# drutest2.net
KiCad netlist of a schematic drawn in EAGLE
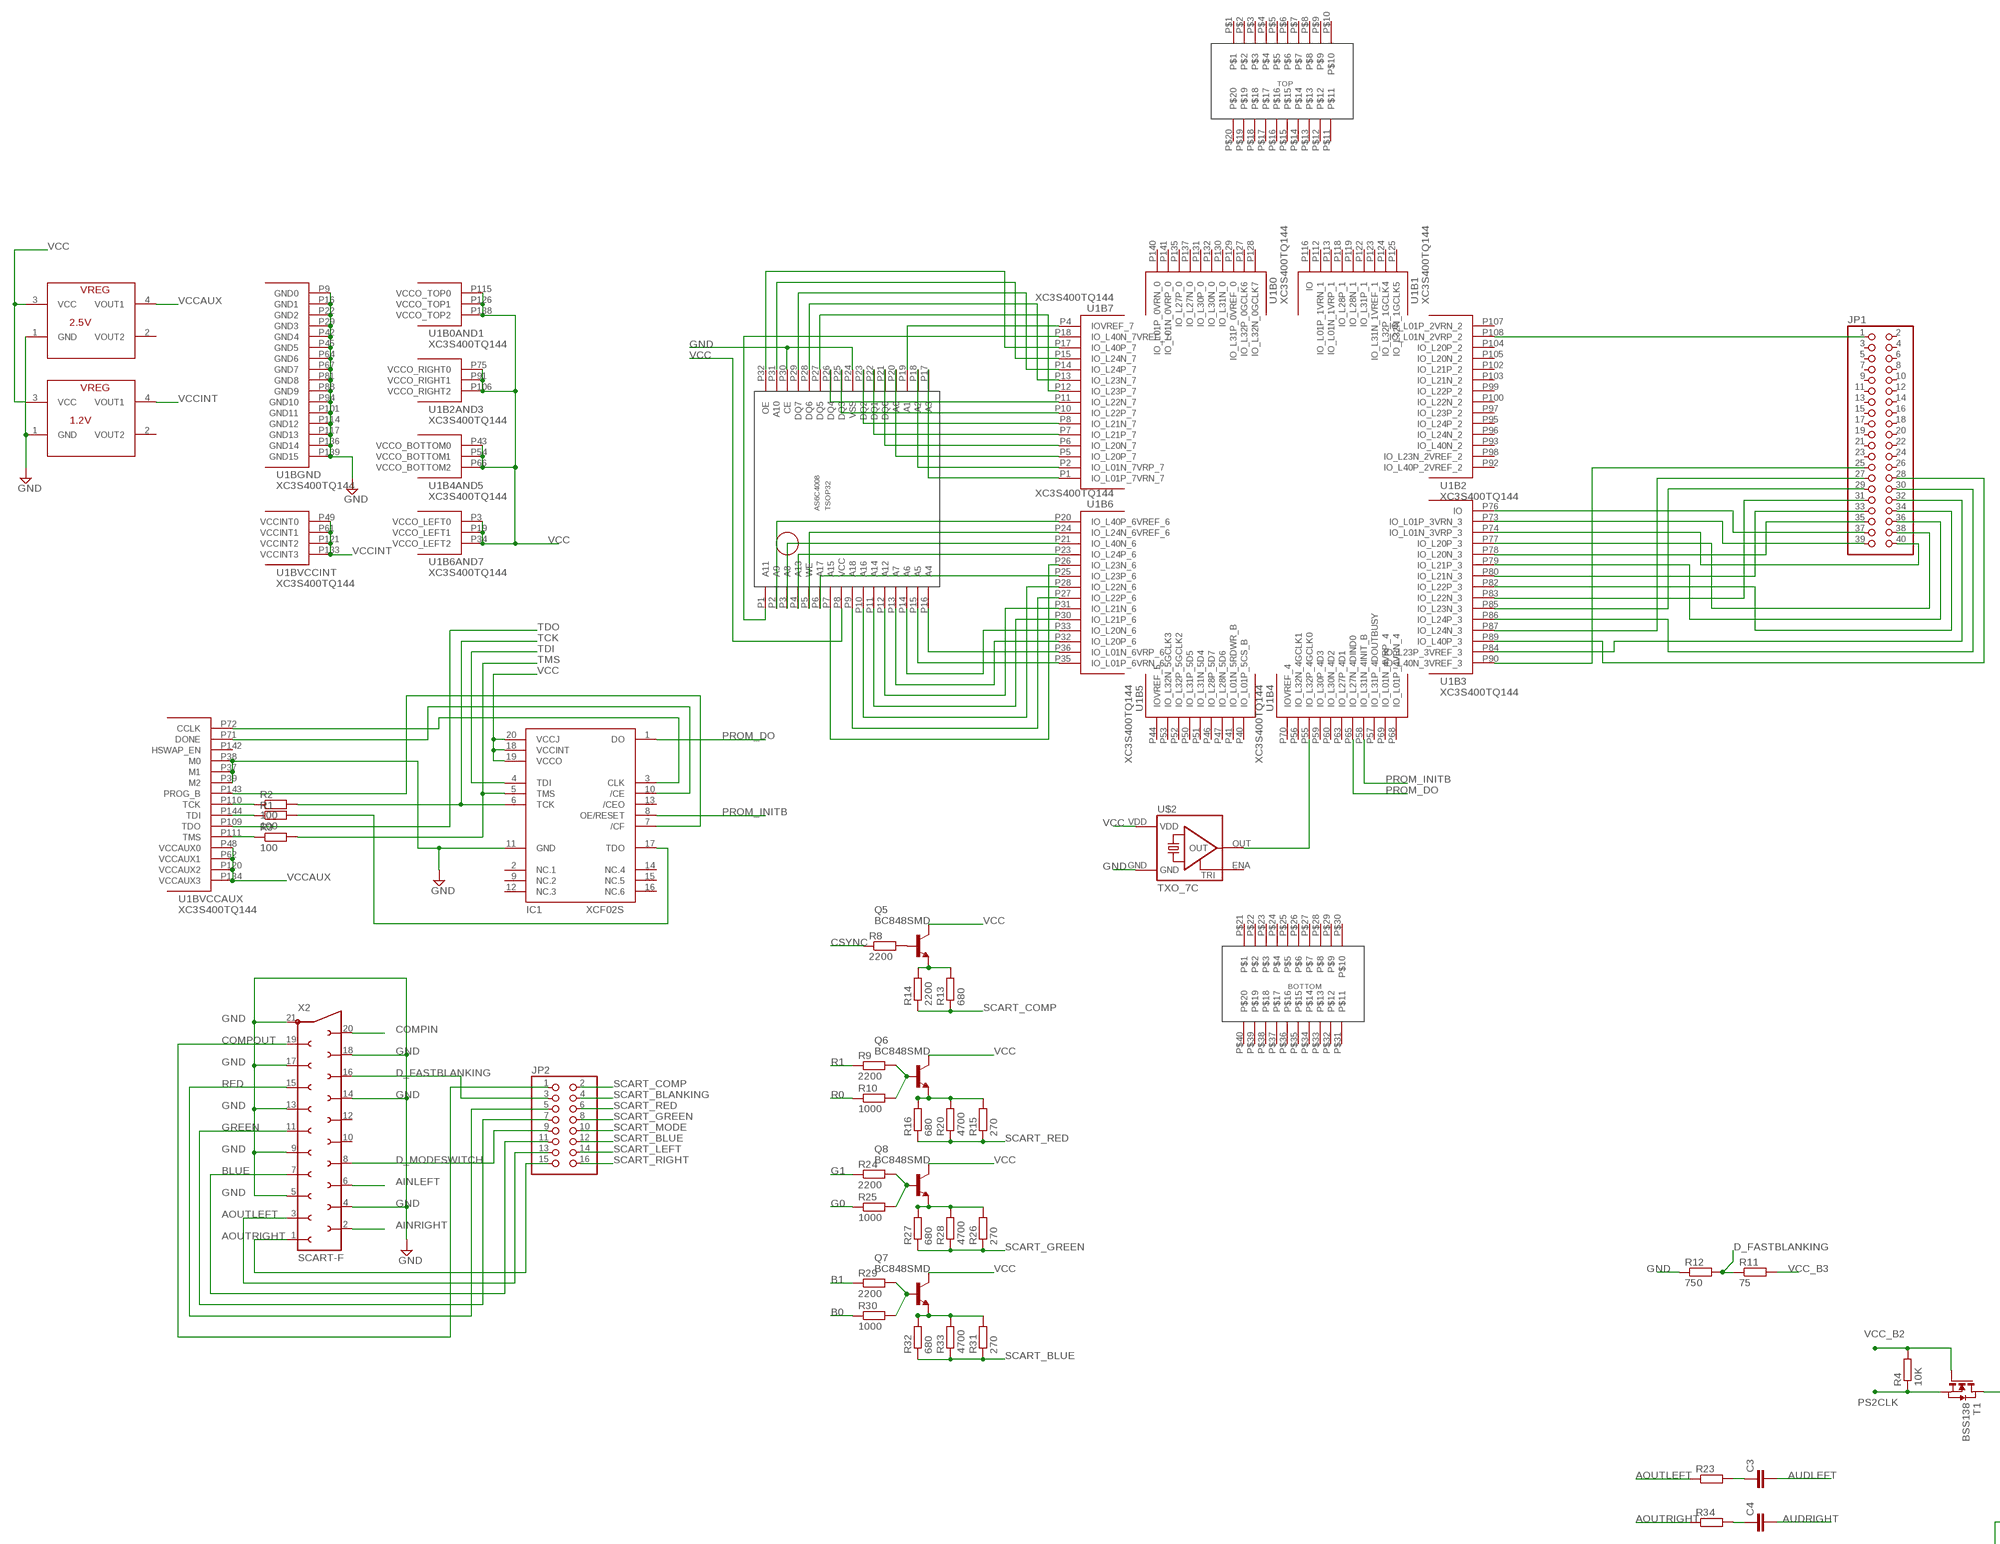
[diagram p0: schematic, sheet 1, part 1 of 2]
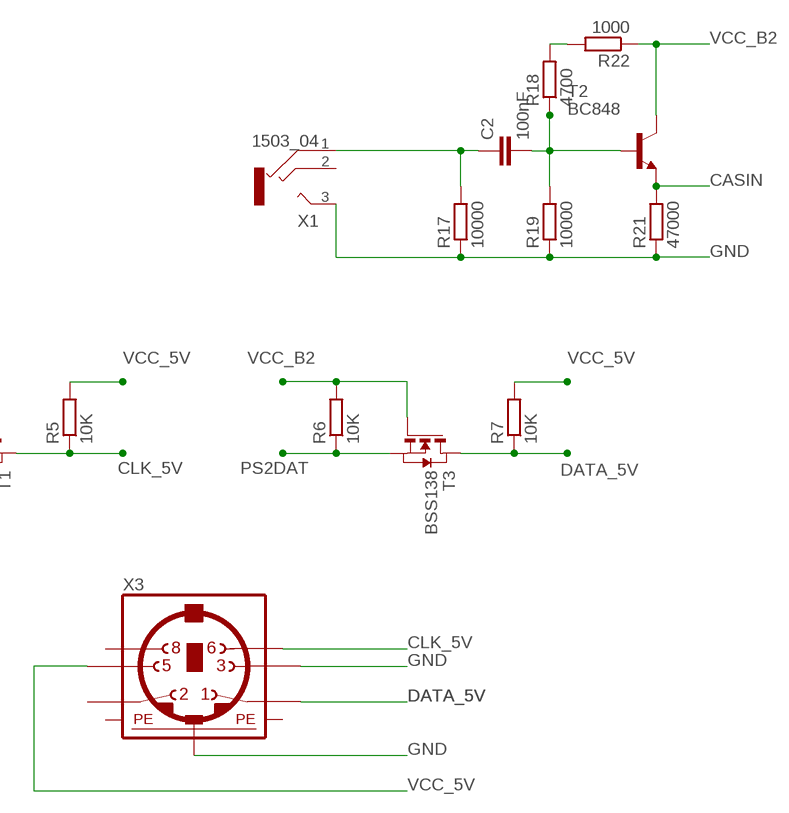
[diagram p1: schematic, sheet 1, part 2 of 2]

(export (version "E")
  (design (tool "Eeschema 10.0.6"))
  (components
    (comp (ref "C2")
      (value "100nF")
      (footprint "eagle-import:C0603")
      (libsource (lib "eagle-import") (part "C-EUC0603"))
    )
    (comp (ref "C3")
      (value "C-EUC0603")
      (footprint "eagle-import:C0603")
      (libsource (lib "eagle-import") (part "C-EUC0603"))
    )
    (comp (ref "C4")
      (value "C-EUC0603")
      (footprint "eagle-import:C0603")
      (libsource (lib "eagle-import") (part "C-EUC0603"))
    )
    (comp (ref "IC1")
      (value "XCF02S")
      (footprint "eagle-import:VO20")
      (libsource (lib "eagle-import") (part "XCF02S"))
    )
    (comp (ref "JP1")
      (value "PINHD-2X20")
      (footprint "eagle-import:2X20")
      (libsource (lib "eagle-import") (part "PINHD-2X20"))
    )
    (comp (ref "JP2")
      (value "PINHD-2X8")
      (footprint "eagle-import:2X08")
      (libsource (lib "eagle-import") (part "PINHD-2X8"))
    )
    (comp (ref "Q5")
      (value "BC848SMD")
      (footprint "eagle-import:SOT23")
      (libsource (lib "eagle-import") (part "BC848SMD"))
    )
    (comp (ref "Q6")
      (value "BC848SMD")
      (footprint "eagle-import:SOT23")
      (libsource (lib "eagle-import") (part "BC848SMD"))
    )
    (comp (ref "Q7")
      (value "BC848SMD")
      (footprint "eagle-import:SOT23")
      (libsource (lib "eagle-import") (part "BC848SMD"))
    )
    (comp (ref "Q8")
      (value "BC848SMD")
      (footprint "eagle-import:SOT23")
      (libsource (lib "eagle-import") (part "BC848SMD"))
    )
    (comp (ref "R1")
      (value "100")
      (footprint "eagle-import:R0805")
      (libsource (lib "eagle-import") (part "R-EU_R0805"))
    )
    (comp (ref "R2")
      (value "100")
      (footprint "eagle-import:R0805")
      (libsource (lib "eagle-import") (part "R-EU_R0805"))
    )
    (comp (ref "R3")
      (value "100")
      (footprint "eagle-import:R0805")
      (libsource (lib "eagle-import") (part "R-EU_R0805"))
    )
    (comp (ref "R4")
      (value "10K")
      (footprint "eagle-import:R0805")
      (libsource (lib "eagle-import") (part "R-EU_R0805"))
    )
    (comp (ref "R5")
      (value "10K")
      (footprint "eagle-import:R0805")
      (libsource (lib "eagle-import") (part "R-EU_R0805"))
    )
    (comp (ref "R6")
      (value "10K")
      (footprint "eagle-import:R0805")
      (libsource (lib "eagle-import") (part "R-EU_R0805"))
    )
    (comp (ref "R7")
      (value "10K")
      (footprint "eagle-import:R0805")
      (libsource (lib "eagle-import") (part "R-EU_R0805"))
    )
    (comp (ref "R8")
      (value "2200")
      (footprint "eagle-import:R0805")
      (libsource (lib "eagle-import") (part "R-EU_R0805"))
    )
    (comp (ref "R9")
      (value "2200")
      (footprint "eagle-import:R0805")
      (libsource (lib "eagle-import") (part "R-EU_R0805"))
    )
    (comp (ref "R10")
      (value "1000")
      (footprint "eagle-import:R0805")
      (libsource (lib "eagle-import") (part "R-EU_R0805"))
    )
    (comp (ref "R11")
      (value "75")
      (footprint "eagle-import:R0805")
      (libsource (lib "eagle-import") (part "R-EU_R0805"))
    )
    (comp (ref "R12")
      (value "750")
      (footprint "eagle-import:R0805")
      (libsource (lib "eagle-import") (part "R-EU_R0805"))
    )
    (comp (ref "R13")
      (value "680")
      (footprint "eagle-import:R0805")
      (libsource (lib "eagle-import") (part "R-EU_R0805"))
    )
    (comp (ref "R14")
      (value "2200")
      (footprint "eagle-import:R0805")
      (libsource (lib "eagle-import") (part "R-EU_R0805"))
    )
    (comp (ref "R15")
      (value "270")
      (footprint "eagle-import:R0805")
      (libsource (lib "eagle-import") (part "R-EU_R0805"))
    )
    (comp (ref "R16")
      (value "680")
      (footprint "eagle-import:R0805")
      (libsource (lib "eagle-import") (part "R-EU_R0805"))
    )
    (comp (ref "R17")
      (value "10000")
      (footprint "eagle-import:R0805")
      (libsource (lib "eagle-import") (part "R-EU_R0805"))
    )
    (comp (ref "R18")
      (value "4700")
      (footprint "eagle-import:R0805")
      (libsource (lib "eagle-import") (part "R-EU_R0805"))
    )
    (comp (ref "R19")
      (value "10000")
      (footprint "eagle-import:R0805")
      (libsource (lib "eagle-import") (part "R-EU_R0805"))
    )
    (comp (ref "R20")
      (value "4700")
      (footprint "eagle-import:R0805")
      (libsource (lib "eagle-import") (part "R-EU_R0805"))
    )
    (comp (ref "R21")
      (value "47000")
      (footprint "eagle-import:R0805")
      (libsource (lib "eagle-import") (part "R-EU_R0805"))
    )
    (comp (ref "R22")
      (value "1000")
      (footprint "eagle-import:R0805")
      (libsource (lib "eagle-import") (part "R-EU_R0805"))
    )
    (comp (ref "R23")
      (value "R-EU_M0805")
      (footprint "eagle-import:M0805")
      (libsource (lib "eagle-import") (part "resistor_R-EU_M0805"))
    )
    (comp (ref "R24")
      (value "2200")
      (footprint "eagle-import:R0805")
      (libsource (lib "eagle-import") (part "R-EU_R0805"))
    )
    (comp (ref "R25")
      (value "1000")
      (footprint "eagle-import:R0805")
      (libsource (lib "eagle-import") (part "R-EU_R0805"))
    )
    (comp (ref "R26")
      (value "270")
      (footprint "eagle-import:R0805")
      (libsource (lib "eagle-import") (part "R-EU_R0805"))
    )
    (comp (ref "R27")
      (value "680")
      (footprint "eagle-import:R0805")
      (libsource (lib "eagle-import") (part "R-EU_R0805"))
    )
    (comp (ref "R28")
      (value "4700")
      (footprint "eagle-import:R0805")
      (libsource (lib "eagle-import") (part "R-EU_R0805"))
    )
    (comp (ref "R29")
      (value "2200")
      (footprint "eagle-import:R0805")
      (libsource (lib "eagle-import") (part "R-EU_R0805"))
    )
    (comp (ref "R30")
      (value "1000")
      (footprint "eagle-import:R0805")
      (libsource (lib "eagle-import") (part "R-EU_R0805"))
    )
    (comp (ref "R31")
      (value "270")
      (footprint "eagle-import:R0805")
      (libsource (lib "eagle-import") (part "R-EU_R0805"))
    )
    (comp (ref "R32")
      (value "680")
      (footprint "eagle-import:R0805")
      (libsource (lib "eagle-import") (part "R-EU_R0805"))
    )
    (comp (ref "R33")
      (value "4700")
      (footprint "eagle-import:R0805")
      (libsource (lib "eagle-import") (part "R-EU_R0805"))
    )
    (comp (ref "R34")
      (value "R-EU_M0805")
      (footprint "eagle-import:M0805")
      (libsource (lib "eagle-import") (part "resistor_R-EU_M0805"))
    )
    (comp (ref "T1")
      (value "BSS138")
      (footprint "eagle-import:SOT-23")
      (libsource (lib "eagle-import") (part "NMOSSOT23"))
    )
    (comp (ref "T2")
      (value "BC848")
      (footprint "eagle-import:SOT23")
      (libsource (lib "eagle-import") (part "BC848"))
    )
    (comp (ref "T3")
      (value "BSS138")
      (footprint "eagle-import:SOT-23")
      (libsource (lib "eagle-import") (part "NMOSSOT23"))
    )
    (comp (ref "U$1")
      (value "AS6C4008")
      (footprint "eagle-import:TSOP32")
      (libsource (lib "eagle-import") (part "AS6C4008"))
    )
    (comp (ref "U$2")
      (value "TXO_7C")
      (footprint "eagle-import:OSC_7C")
      (libsource (lib "eagle-import") (part "TXO_7C"))
    )
    (comp (ref "U$3")
      (value "2.5V")
      (footprint "eagle-import:SOT223")
      (libsource (lib "eagle-import") (part "NX1117"))
    )
    (comp (ref "U$4")
      (value "1.2V")
      (footprint "eagle-import:SOT223")
      (libsource (lib "eagle-import") (part "NX1117"))
    )
    (comp (ref "U$5")
      (value "EXPHDR")
      (footprint "eagle-import:EXPHDR")
      (libsource (lib "eagle-import") (part "EXPHDR"))
    )
    (comp (ref "U1")
      (value "XC3S400TQ144")
      (footprint "eagle-import:TQ144")
      (libsource (lib "eagle-import") (part "XC3S400TQ144"))
    )
    (comp (ref "X1")
      (value "1503_04")
      (footprint "eagle-import:1503_04")
      (libsource (lib "eagle-import") (part "1503_04"))
    )
    (comp (ref "X2")
      (value "SCART-F")
      (footprint "eagle-import:SCART-F")
      (libsource (lib "eagle-import") (part "SCART-F"))
    )
    (comp (ref "X3")
      (value "MINI_DIN_6")
      (footprint "eagle-import:M_DIN6")
      (libsource (lib "eagle-import") (part "MINI_DIN_6"))
    )
  )
  (nets
    (net (code "1") (name "/AINLEFT") (class "Default")
      (node (ref "X2") (pin "6") (pinfunction "6_6") (pintype "passive"))
    )
    (net (code "2") (name "/AINRIGHT") (class "Default")
      (node (ref "X2") (pin "2") (pinfunction "2_2") (pintype "passive"))
    )
    (net (code "3") (name "/AOUTLEFT") (class "Default")
      (node (ref "JP2") (pin "13") (pinfunction "13_13") (pintype "passive"))
      (node (ref "R23") (pin "1") (pinfunction "1_1") (pintype "passive"))
      (node (ref "X2") (pin "3") (pinfunction "3_3") (pintype "passive"))
    )
    (net (code "4") (name "/AOUTRIGHT") (class "Default")
      (node (ref "JP2") (pin "15") (pinfunction "15_15") (pintype "passive"))
      (node (ref "R34") (pin "1") (pinfunction "1_1") (pintype "passive"))
      (node (ref "X2") (pin "1") (pinfunction "1_1") (pintype "passive"))
    )
    (net (code "5") (name "/AUDLEFT") (class "Default")
      (node (ref "C3") (pin "2") (pinfunction "2_2") (pintype "passive"))
    )
    (net (code "6") (name "/AUDRIGHT") (class "Default")
      (node (ref "C4") (pin "2") (pinfunction "2_2") (pintype "passive"))
    )
    (net (code "7") (name "/B0") (class "Default")
      (node (ref "R30") (pin "1") (pinfunction "1_1") (pintype "passive"))
    )
    (net (code "8") (name "/B1") (class "Default")
      (node (ref "R29") (pin "1") (pinfunction "1_1") (pintype "passive"))
    )
    (net (code "9") (name "/BLUE") (class "Default")
      (node (ref "JP2") (pin "11") (pinfunction "11_11") (pintype "passive"))
      (node (ref "X2") (pin "7") (pinfunction "7_7") (pintype "passive"))
    )
    (net (code "10") (name "/CASIN") (class "Default")
      (node (ref "R21") (pin "2") (pinfunction "2_2") (pintype "passive"))
      (node (ref "T2") (pin "2") (pinfunction "E_2") (pintype "passive"))
    )
    (net (code "11") (name "/CLK_5V") (class "Default")
      (node (ref "R5") (pin "1") (pinfunction "1_1") (pintype "passive"))
      (node (ref "T1") (pin "1") (pinfunction "D_1") (pintype "passive"))
      (node (ref "X3") (pin "6") (pinfunction "6_6") (pintype "passive"))
    )
    (net (code "12") (name "/COMPIN") (class "Default")
      (node (ref "X2") (pin "20") (pinfunction "20_20") (pintype "passive"))
    )
    (net (code "13") (name "/COMPOUT") (class "Default")
      (node (ref "JP2") (pin "1") (pinfunction "1_1") (pintype "passive"))
      (node (ref "X2") (pin "19") (pinfunction "19_19") (pintype "passive"))
    )
    (net (code "14") (name "/CSYNC") (class "Default")
      (node (ref "R8") (pin "1") (pinfunction "1_1") (pintype "passive"))
    )
    (net (code "15") (name "/DATA_5V") (class "Default")
      (node (ref "R7") (pin "1") (pinfunction "1_1") (pintype "passive"))
      (node (ref "T3") (pin "1") (pinfunction "D_1") (pintype "passive"))
      (node (ref "X3") (pin "1") (pinfunction "1_1") (pintype "passive"))
    )
    (net (code "16") (name "/D_FASTBLANKING") (class "Default")
      (node (ref "JP2") (pin "3") (pinfunction "3_3") (pintype "passive"))
      (node (ref "R11") (pin "1") (pinfunction "1_1") (pintype "passive"))
      (node (ref "R12") (pin "2") (pinfunction "2_2") (pintype "passive"))
      (node (ref "X2") (pin "16") (pinfunction "16_16") (pintype "passive"))
    )
    (net (code "17") (name "/D_MODESWITCH") (class "Default")
      (node (ref "JP2") (pin "9") (pinfunction "9_9") (pintype "passive"))
      (node (ref "X2") (pin "8") (pinfunction "8_8") (pintype "passive"))
    )
    (net (code "18") (name "/G0") (class "Default")
      (node (ref "R25") (pin "1") (pinfunction "1_1") (pintype "passive"))
    )
    (net (code "19") (name "/G1") (class "Default")
      (node (ref "R24") (pin "1") (pinfunction "1_1") (pintype "passive"))
    )
    (net (code "20") (name "/GREEN") (class "Default")
      (node (ref "JP2") (pin "7") (pinfunction "7_7") (pintype "passive"))
      (node (ref "X2") (pin "11") (pinfunction "11_11") (pintype "passive"))
    )
    (net (code "21") (name "/PE1") (class "Default")
      (node (ref "X3") (pin "SH1") (pinfunction "PE1_SH1") (pintype "power_in"))
    )
    (net (code "22") (name "/PE3") (class "Default")
      (node (ref "X3") (pin "SH3") (pinfunction "PE3_SH3") (pintype "power_in"))
    )
    (net (code "23") (name "/PROM_DO") (class "Default")
      (node (ref "IC1") (pin "1") (pinfunction "DO_1") (pintype "bidirectional"))
      (node (ref "U1") (pin "P65") (pinfunction "IO_L27N_4DIND0_P65") (pintype "bidirectional"))
    )
    (net (code "24") (name "/PROM_INITB") (class "Default")
      (node (ref "IC1") (pin "8") (pinfunction "OE/RESET_8") (pintype "bidirectional"))
      (node (ref "U1") (pin "P58") (pinfunction "IO_L31N_4INIT_B_P58") (pintype "bidirectional"))
    )
    (net (code "25") (name "/PS2CLK") (class "Default")
      (node (ref "R4") (pin "1") (pinfunction "1_1") (pintype "passive"))
      (node (ref "T1") (pin "2") (pinfunction "S_2") (pintype "passive"))
    )
    (net (code "26") (name "/PS2DAT") (class "Default")
      (node (ref "R6") (pin "1") (pinfunction "1_1") (pintype "passive"))
      (node (ref "T3") (pin "2") (pinfunction "S_2") (pintype "passive"))
    )
    (net (code "27") (name "/R0") (class "Default")
      (node (ref "R10") (pin "1") (pinfunction "1_1") (pintype "passive"))
    )
    (net (code "28") (name "/R1") (class "Default")
      (node (ref "R9") (pin "1") (pinfunction "1_1") (pintype "passive"))
    )
    (net (code "29") (name "/RED") (class "Default")
      (node (ref "JP2") (pin "5") (pinfunction "5_5") (pintype "passive"))
      (node (ref "X2") (pin "15") (pinfunction "15_15") (pintype "passive"))
    )
    (net (code "30") (name "/SCART_BLANKING") (class "Default")
      (node (ref "JP2") (pin "4") (pinfunction "4_4") (pintype "passive"))
    )
    (net (code "31") (name "/SCART_BLUE") (class "Default")
      (node (ref "JP2") (pin "12") (pinfunction "12_12") (pintype "passive"))
      (node (ref "R31") (pin "1") (pinfunction "1_1") (pintype "passive"))
      (node (ref "R32") (pin "1") (pinfunction "1_1") (pintype "passive"))
      (node (ref "R33") (pin "1") (pinfunction "1_1") (pintype "passive"))
    )
    (net (code "32") (name "/SCART_COMP") (class "Default")
      (node (ref "JP2") (pin "2") (pinfunction "2_2") (pintype "passive"))
      (node (ref "R13") (pin "1") (pinfunction "1_1") (pintype "passive"))
      (node (ref "R14") (pin "1") (pinfunction "1_1") (pintype "passive"))
    )
    (net (code "33") (name "/SCART_GREEN") (class "Default")
      (node (ref "JP2") (pin "8") (pinfunction "8_8") (pintype "passive"))
      (node (ref "R26") (pin "1") (pinfunction "1_1") (pintype "passive"))
      (node (ref "R27") (pin "1") (pinfunction "1_1") (pintype "passive"))
      (node (ref "R28") (pin "1") (pinfunction "1_1") (pintype "passive"))
    )
    (net (code "34") (name "/SCART_LEFT") (class "Default")
      (node (ref "JP2") (pin "14") (pinfunction "14_14") (pintype "passive"))
    )
    (net (code "35") (name "/SCART_MODE") (class "Default")
      (node (ref "JP2") (pin "10") (pinfunction "10_10") (pintype "passive"))
    )
    (net (code "36") (name "/SCART_RED") (class "Default")
      (node (ref "JP2") (pin "6") (pinfunction "6_6") (pintype "passive"))
      (node (ref "R15") (pin "1") (pinfunction "1_1") (pintype "passive"))
      (node (ref "R16") (pin "1") (pinfunction "1_1") (pintype "passive"))
      (node (ref "R20") (pin "1") (pinfunction "1_1") (pintype "passive"))
    )
    (net (code "37") (name "/SCART_RIGHT") (class "Default")
      (node (ref "JP2") (pin "16") (pinfunction "16_16") (pintype "passive"))
    )
    (net (code "38") (name "/TCK") (class "Default")
      (node (ref "IC1") (pin "6") (pinfunction "TCK_6") (pintype "bidirectional"))
      (node (ref "R2") (pin "2") (pinfunction "2_2") (pintype "passive"))
    )
    (net (code "39") (name "/TDI") (class "Default")
      (node (ref "IC1") (pin "4") (pinfunction "TDI_4") (pintype "bidirectional"))
    )
    (net (code "40") (name "/TDO") (class "Default")
      (node (ref "U1") (pin "P109") (pinfunction "TDO_P109") (pintype "bidirectional"))
    )
    (net (code "41") (name "/TMS") (class "Default")
      (node (ref "IC1") (pin "5") (pinfunction "TMS_5") (pintype "bidirectional"))
      (node (ref "R3") (pin "2") (pinfunction "2_2") (pintype "passive"))
    )
    (net (code "42") (name "/VCC") (class "Default")
      (node (ref "IC1") (pin "18") (pinfunction "VCCINT_18") (pintype "bidirectional"))
      (node (ref "IC1") (pin "19") (pinfunction "VCCO_19") (pintype "bidirectional"))
      (node (ref "IC1") (pin "20") (pinfunction "VCCJ_20") (pintype "bidirectional"))
      (node (ref "Q5") (pin "3") (pinfunction "C_3") (pintype "passive"))
      (node (ref "Q6") (pin "3") (pinfunction "C_3") (pintype "passive"))
      (node (ref "Q7") (pin "3") (pinfunction "C_3") (pintype "passive"))
      (node (ref "Q8") (pin "3") (pinfunction "C_3") (pintype "passive"))
      (node (ref "U$1") (pin "P8") (pinfunction "VCC_P8") (pintype "bidirectional"))
      (node (ref "U$2") (pin "VDD") (pinfunction "VDD_VDD") (pintype "power_in"))
      (node (ref "U$3") (pin "3") (pinfunction "VCC_3") (pintype "bidirectional"))
      (node (ref "U$4") (pin "3") (pinfunction "VCC_3") (pintype "bidirectional"))
      (node (ref "U1") (pin "P106") (pinfunction "VCCO_RIGHT2_P106") (pintype "passive"))
      (node (ref "U1") (pin "P115") (pinfunction "VCCO_TOP0_P115") (pintype "passive"))
      (node (ref "U1") (pin "P126") (pinfunction "VCCO_TOP1_P126") (pintype "passive"))
      (node (ref "U1") (pin "P138") (pinfunction "VCCO_TOP2_P138") (pintype "passive"))
      (node (ref "U1") (pin "P19") (pinfunction "VCCO_LEFT1_P19") (pintype "passive"))
      (node (ref "U1") (pin "P3") (pinfunction "VCCO_LEFT0_P3") (pintype "passive"))
      (node (ref "U1") (pin "P34") (pinfunction "VCCO_LEFT2_P34") (pintype "passive"))
      (node (ref "U1") (pin "P43") (pinfunction "VCCO_BOTTOM0_P43") (pintype "passive"))
      (node (ref "U1") (pin "P54") (pinfunction "VCCO_BOTTOM1_P54") (pintype "passive"))
      (node (ref "U1") (pin "P66") (pinfunction "VCCO_BOTTOM2_P66") (pintype "passive"))
      (node (ref "U1") (pin "P75") (pinfunction "VCCO_RIGHT0_P75") (pintype "passive"))
      (node (ref "U1") (pin "P91") (pinfunction "VCCO_RIGHT1_P91") (pintype "passive"))
    )
    (net (code "43") (name "/VCCAUX") (class "Default")
      (node (ref "U$3") (pin "4") (pinfunction "VOUT1_4") (pintype "bidirectional"))
      (node (ref "U1") (pin "P120") (pinfunction "VCCAUX2_P120") (pintype "passive"))
      (node (ref "U1") (pin "P134") (pinfunction "VCCAUX3_P134") (pintype "passive"))
      (node (ref "U1") (pin "P48") (pinfunction "VCCAUX0_P48") (pintype "passive"))
      (node (ref "U1") (pin "P62") (pinfunction "VCCAUX1_P62") (pintype "passive"))
    )
    (net (code "44") (name "/VCCINT") (class "Default")
      (node (ref "U$4") (pin "4") (pinfunction "VOUT1_4") (pintype "bidirectional"))
      (node (ref "U1") (pin "P121") (pinfunction "VCCINT2_P121") (pintype "passive"))
      (node (ref "U1") (pin "P133") (pinfunction "VCCINT3_P133") (pintype "passive"))
      (node (ref "U1") (pin "P49") (pinfunction "VCCINT0_P49") (pintype "passive"))
      (node (ref "U1") (pin "P61") (pinfunction "VCCINT1_P61") (pintype "passive"))
    )
    (net (code "45") (name "/VCC_5V") (class "Default")
      (node (ref "R5") (pin "2") (pinfunction "2_2") (pintype "passive"))
      (node (ref "R7") (pin "2") (pinfunction "2_2") (pintype "passive"))
      (node (ref "X3") (pin "5") (pinfunction "5_5") (pintype "passive"))
    )
    (net (code "46") (name "/VCC_B2") (class "Default")
      (node (ref "R22") (pin "1") (pinfunction "1_1") (pintype "passive"))
      (node (ref "R4") (pin "2") (pinfunction "2_2") (pintype "passive"))
      (node (ref "R6") (pin "2") (pinfunction "2_2") (pintype "passive"))
      (node (ref "T1") (pin "3") (pinfunction "G_3") (pintype "passive"))
      (node (ref "T2") (pin "3") (pinfunction "C_3") (pintype "passive"))
      (node (ref "T3") (pin "3") (pinfunction "G_3") (pintype "passive"))
    )
    (net (code "47") (name "/VCC_B3") (class "Default")
      (node (ref "R11") (pin "2") (pinfunction "2_2") (pintype "passive"))
    )
    (net (code "48") (name "GND") (class "Default")
      (node (ref "IC1") (pin "11") (pinfunction "GND_11") (pintype "bidirectional"))
      (node (ref "R12") (pin "1") (pinfunction "1_1") (pintype "passive"))
      (node (ref "R17") (pin "1") (pinfunction "1_1") (pintype "passive"))
      (node (ref "R19") (pin "1") (pinfunction "1_1") (pintype "passive"))
      (node (ref "R21") (pin "1") (pinfunction "1_1") (pintype "passive"))
      (node (ref "U$1") (pin "P24") (pinfunction "VSS_P24") (pintype "bidirectional"))
      (node (ref "U$1") (pin "P30") (pinfunction "CE_P30") (pintype "bidirectional"))
      (node (ref "U$2") (pin "GND") (pinfunction "GND_GND") (pintype "power_in"))
      (node (ref "U$3") (pin "1") (pinfunction "GND_1") (pintype "bidirectional"))
      (node (ref "U$4") (pin "1") (pinfunction "GND_1") (pintype "bidirectional"))
      (node (ref "U1") (pin "P101") (pinfunction "GND11_P101") (pintype "passive"))
      (node (ref "U1") (pin "P114") (pinfunction "GND12_P114") (pintype "passive"))
      (node (ref "U1") (pin "P117") (pinfunction "GND13_P117") (pintype "passive"))
      (node (ref "U1") (pin "P136") (pinfunction "GND14_P136") (pintype "passive"))
      (node (ref "U1") (pin "P139") (pinfunction "GND15_P139") (pintype "passive"))
      (node (ref "U1") (pin "P16") (pinfunction "GND1_P16") (pintype "passive"))
      (node (ref "U1") (pin "P22") (pinfunction "GND2_P22") (pintype "passive"))
      (node (ref "U1") (pin "P29") (pinfunction "GND3_P29") (pintype "passive"))
      (node (ref "U1") (pin "P37") (pinfunction "M1_P37") (pintype "bidirectional"))
      (node (ref "U1") (pin "P38") (pinfunction "M0_P38") (pintype "bidirectional"))
      (node (ref "U1") (pin "P39") (pinfunction "M2_P39") (pintype "bidirectional"))
      (node (ref "U1") (pin "P42") (pinfunction "GND4_P42") (pintype "passive"))
      (node (ref "U1") (pin "P45") (pinfunction "GND5_P45") (pintype "passive"))
      (node (ref "U1") (pin "P64") (pinfunction "GND6_P64") (pintype "passive"))
      (node (ref "U1") (pin "P67") (pinfunction "GND7_P67") (pintype "passive"))
      (node (ref "U1") (pin "P81") (pinfunction "GND8_P81") (pintype "passive"))
      (node (ref "U1") (pin "P88") (pinfunction "GND9_P88") (pintype "passive"))
      (node (ref "U1") (pin "P9") (pinfunction "GND0_P9") (pintype "passive"))
      (node (ref "U1") (pin "P94") (pinfunction "GND10_P94") (pintype "passive"))
      (node (ref "X1") (pin "3") (pinfunction "2_3") (pintype "passive"))
      (node (ref "X2") (pin "13") (pinfunction "13_13") (pintype "passive"))
      (node (ref "X2") (pin "14") (pinfunction "14_14") (pintype "passive"))
      (node (ref "X2") (pin "17") (pinfunction "17_17") (pintype "passive"))
      (node (ref "X2") (pin "18") (pinfunction "18_18") (pintype "passive"))
      (node (ref "X2") (pin "21") (pinfunction "21_21") (pintype "passive"))
      (node (ref "X2") (pin "4") (pinfunction "4_4") (pintype "passive"))
      (node (ref "X2") (pin "5") (pinfunction "5_5") (pintype "passive"))
      (node (ref "X2") (pin "9") (pinfunction "9_9") (pintype "passive"))
      (node (ref "X3") (pin "3") (pinfunction "3_3") (pintype "passive"))
      (node (ref "X3") (pin "SH2") (pinfunction "PE2_SH2") (pintype "power_in"))
    )
    (net (code "49") (name "Net-(C2-Pad1)") (class "Default")
      (node (ref "C2") (pin "1") (pinfunction "1_1") (pintype "passive"))
      (node (ref "R17") (pin "2") (pinfunction "2_2") (pintype "passive"))
      (node (ref "X1") (pin "1") (pinfunction "1_1") (pintype "passive"))
    )
    (net (code "50") (name "Net-(C3-Pad1)") (class "Default")
      (node (ref "C3") (pin "1") (pinfunction "1_1") (pintype "passive"))
      (node (ref "R23") (pin "2") (pinfunction "2_2") (pintype "passive"))
    )
    (net (code "51") (name "Net-(C4-Pad1)") (class "Default")
      (node (ref "C4") (pin "1") (pinfunction "1_1") (pintype "passive"))
      (node (ref "R34") (pin "2") (pinfunction "2_2") (pintype "passive"))
    )
    (net (code "52") (name "Net-(IC1-CLK)") (class "Default")
      (node (ref "IC1") (pin "3") (pinfunction "CLK_3") (pintype "bidirectional"))
      (node (ref "U1") (pin "P72") (pinfunction "CCLK_P72") (pintype "bidirectional"))
    )
    (net (code "53") (name "Net-(IC1-TDO)") (class "Default")
      (node (ref "IC1") (pin "17") (pinfunction "TDO_17") (pintype "bidirectional"))
      (node (ref "R1") (pin "2") (pinfunction "2_2") (pintype "passive"))
    )
    (net (code "54") (name "Net-(IC1-{slash}CE)") (class "Default")
      (node (ref "IC1") (pin "10") (pinfunction "/CE_10") (pintype "bidirectional"))
      (node (ref "U1") (pin "P71") (pinfunction "DONE_P71") (pintype "bidirectional"))
    )
    (net (code "55") (name "Net-(IC1-{slash}CF)") (class "Default")
      (node (ref "IC1") (pin "7") (pinfunction "/CF_7") (pintype "bidirectional"))
      (node (ref "U1") (pin "P143") (pinfunction "PROG_B_P143") (pintype "bidirectional"))
    )
    (net (code "56") (name "Net-(Q5-B)") (class "Default")
      (node (ref "Q5") (pin "1") (pinfunction "B_1") (pintype "passive"))
      (node (ref "R8") (pin "2") (pinfunction "2_2") (pintype "passive"))
    )
    (net (code "57") (name "Net-(Q5-E)") (class "Default")
      (node (ref "Q5") (pin "2") (pinfunction "E_2") (pintype "passive"))
      (node (ref "R13") (pin "2") (pinfunction "2_2") (pintype "passive"))
      (node (ref "R14") (pin "2") (pinfunction "2_2") (pintype "passive"))
    )
    (net (code "58") (name "Net-(Q6-B)") (class "Default")
      (node (ref "Q6") (pin "1") (pinfunction "B_1") (pintype "passive"))
      (node (ref "R10") (pin "2") (pinfunction "2_2") (pintype "passive"))
      (node (ref "R9") (pin "2") (pinfunction "2_2") (pintype "passive"))
    )
    (net (code "59") (name "Net-(Q6-E)") (class "Default")
      (node (ref "Q6") (pin "2") (pinfunction "E_2") (pintype "passive"))
      (node (ref "R15") (pin "2") (pinfunction "2_2") (pintype "passive"))
      (node (ref "R16") (pin "2") (pinfunction "2_2") (pintype "passive"))
      (node (ref "R20") (pin "2") (pinfunction "2_2") (pintype "passive"))
    )
    (net (code "60") (name "Net-(Q7-B)") (class "Default")
      (node (ref "Q7") (pin "1") (pinfunction "B_1") (pintype "passive"))
      (node (ref "R29") (pin "2") (pinfunction "2_2") (pintype "passive"))
      (node (ref "R30") (pin "2") (pinfunction "2_2") (pintype "passive"))
    )
    (net (code "61") (name "Net-(Q7-E)") (class "Default")
      (node (ref "Q7") (pin "2") (pinfunction "E_2") (pintype "passive"))
      (node (ref "R31") (pin "2") (pinfunction "2_2") (pintype "passive"))
      (node (ref "R32") (pin "2") (pinfunction "2_2") (pintype "passive"))
      (node (ref "R33") (pin "2") (pinfunction "2_2") (pintype "passive"))
    )
    (net (code "62") (name "Net-(Q8-B)") (class "Default")
      (node (ref "Q8") (pin "1") (pinfunction "B_1") (pintype "passive"))
      (node (ref "R24") (pin "2") (pinfunction "2_2") (pintype "passive"))
      (node (ref "R25") (pin "2") (pinfunction "2_2") (pintype "passive"))
    )
    (net (code "63") (name "Net-(Q8-E)") (class "Default")
      (node (ref "Q8") (pin "2") (pinfunction "E_2") (pintype "passive"))
      (node (ref "R26") (pin "2") (pinfunction "2_2") (pintype "passive"))
      (node (ref "R27") (pin "2") (pinfunction "2_2") (pintype "passive"))
      (node (ref "R28") (pin "2") (pinfunction "2_2") (pintype "passive"))
    )
    (net (code "64") (name "Net-(R18-Pad2)") (class "Default")
      (node (ref "R18") (pin "2") (pinfunction "2_2") (pintype "passive"))
      (node (ref "R22") (pin "2") (pinfunction "2_2") (pintype "passive"))
    )
    (net (code "65") (name "Net-(T2-B)") (class "Default")
      (node (ref "C2") (pin "2") (pinfunction "2_2") (pintype "passive"))
      (node (ref "R18") (pin "1") (pinfunction "1_1") (pintype "passive"))
      (node (ref "R19") (pin "2") (pinfunction "2_2") (pintype "passive"))
      (node (ref "T2") (pin "1") (pinfunction "B_1") (pintype "passive"))
    )
    (net (code "66") (name "Net-(U$1-A0)") (class "Default")
      (node (ref "U$1") (pin "P20") (pinfunction "A0_P20") (pintype "bidirectional"))
      (node (ref "U1") (pin "P5") (pinfunction "IO_L20P_7_P5") (pintype "bidirectional"))
    )
    (net (code "67") (name "Net-(U$1-A1)") (class "Default")
      (node (ref "U$1") (pin "P19") (pinfunction "A1_P19") (pintype "bidirectional"))
      (node (ref "U1") (pin "P4") (pinfunction "IOVREF_7_P4") (pintype "bidirectional"))
    )
    (net (code "68") (name "Net-(U$1-A2)") (class "Default")
      (node (ref "U$1") (pin "P18") (pinfunction "A2_P18") (pintype "bidirectional"))
      (node (ref "U1") (pin "P2") (pinfunction "IO_L01N_7VRP_7_P2") (pintype "bidirectional"))
    )
    (net (code "69") (name "Net-(U$1-A3)") (class "Default")
      (node (ref "U$1") (pin "P17") (pinfunction "A3_P17") (pintype "bidirectional"))
      (node (ref "U1") (pin "P1") (pinfunction "IO_L01P_7VRN_7_P1") (pintype "bidirectional"))
    )
    (net (code "70") (name "Net-(U$1-A4)") (class "Default")
      (node (ref "U$1") (pin "P16") (pinfunction "A4_P16") (pintype "bidirectional"))
      (node (ref "U1") (pin "P36") (pinfunction "IO_L01N_6VRP_6_P36") (pintype "bidirectional"))
    )
    (net (code "71") (name "Net-(U$1-A5)") (class "Default")
      (node (ref "U$1") (pin "P15") (pinfunction "A5_P15") (pintype "bidirectional"))
      (node (ref "U1") (pin "P35") (pinfunction "IO_L01P_6VRN_6_P35") (pintype "bidirectional"))
    )
    (net (code "72") (name "Net-(U$1-A6)") (class "Default")
      (node (ref "U$1") (pin "P14") (pinfunction "A6_P14") (pintype "bidirectional"))
      (node (ref "U1") (pin "P33") (pinfunction "IO_L20N_6_P33") (pintype "bidirectional"))
    )
    (net (code "73") (name "Net-(U$1-A7)") (class "Default")
      (node (ref "U$1") (pin "P13") (pinfunction "A7_P13") (pintype "bidirectional"))
      (node (ref "U1") (pin "P32") (pinfunction "IO_L20P_6_P32") (pintype "bidirectional"))
    )
    (net (code "74") (name "Net-(U$1-A8)") (class "Default")
      (node (ref "U$1") (pin "P3") (pinfunction "A8_P3") (pintype "bidirectional"))
      (node (ref "U1") (pin "P21") (pinfunction "IO_L40N_6_P21") (pintype "bidirectional"))
    )
    (net (code "75") (name "Net-(U$1-A9)") (class "Default")
      (node (ref "U$1") (pin "P2") (pinfunction "A9_P2") (pintype "bidirectional"))
      (node (ref "U1") (pin "P20") (pinfunction "IO_L40P_6VREF_6_P20") (pintype "bidirectional"))
    )
    (net (code "76") (name "Net-(U$1-A10)") (class "Default")
      (node (ref "U$1") (pin "P31") (pinfunction "A10_P31") (pintype "bidirectional"))
      (node (ref "U1") (pin "P15") (pinfunction "IO_L24N_7_P15") (pintype "bidirectional"))
    )
    (net (code "77") (name "Net-(U$1-A11)") (class "Default")
      (node (ref "U$1") (pin "P1") (pinfunction "A11_P1") (pintype "bidirectional"))
      (node (ref "U1") (pin "P18") (pinfunction "IO_L40N_7VREF_7_P18") (pintype "bidirectional"))
    )
    (net (code "78") (name "Net-(U$1-A12)") (class "Default")
      (node (ref "U$1") (pin "P12") (pinfunction "A12_P12") (pintype "bidirectional"))
      (node (ref "U1") (pin "P31") (pinfunction "IO_L21N_6_P31") (pintype "bidirectional"))
    )
    (net (code "79") (name "Net-(U$1-A13)") (class "Default")
      (node (ref "U$1") (pin "P4") (pinfunction "A13_P4") (pintype "bidirectional"))
      (node (ref "U1") (pin "P23") (pinfunction "IO_L24P_6_P23") (pintype "bidirectional"))
    )
    (net (code "80") (name "Net-(U$1-A14)") (class "Default")
      (node (ref "U$1") (pin "P11") (pinfunction "A14_P11") (pintype "bidirectional"))
      (node (ref "U1") (pin "P30") (pinfunction "IO_L21P_6_P30") (pintype "bidirectional"))
    )
    (net (code "81") (name "Net-(U$1-A15)") (class "Default")
      (node (ref "U$1") (pin "P7") (pinfunction "A15_P7") (pintype "bidirectional"))
      (node (ref "U1") (pin "P26") (pinfunction "IO_L23N_6_P26") (pintype "bidirectional"))
    )
    (net (code "82") (name "Net-(U$1-A16)") (class "Default")
      (node (ref "U$1") (pin "P10") (pinfunction "A16_P10") (pintype "bidirectional"))
      (node (ref "U1") (pin "P28") (pinfunction "IO_L22N_6_P28") (pintype "bidirectional"))
    )
    (net (code "83") (name "Net-(U$1-A17)") (class "Default")
      (node (ref "U$1") (pin "P6") (pinfunction "A17_P6") (pintype "bidirectional"))
      (node (ref "U1") (pin "P25") (pinfunction "IO_L23P_6_P25") (pintype "bidirectional"))
    )
    (net (code "84") (name "Net-(U$1-A18)") (class "Default")
      (node (ref "U$1") (pin "P9") (pinfunction "A18_P9") (pintype "bidirectional"))
      (node (ref "U1") (pin "P27") (pinfunction "IO_L22P_6_P27") (pintype "bidirectional"))
    )
    (net (code "85") (name "Net-(U$1-DQ0)") (class "Default")
      (node (ref "U$1") (pin "P21") (pinfunction "DQ0_P21") (pintype "bidirectional"))
      (node (ref "U1") (pin "P6") (pinfunction "IO_L20N_7_P6") (pintype "bidirectional"))
    )
    (net (code "86") (name "Net-(U$1-DQ1)") (class "Default")
      (node (ref "U$1") (pin "P22") (pinfunction "DQ1_P22") (pintype "bidirectional"))
      (node (ref "U1") (pin "P7") (pinfunction "IO_L21P_7_P7") (pintype "bidirectional"))
    )
    (net (code "87") (name "Net-(U$1-DQ2)") (class "Default")
      (node (ref "U$1") (pin "P23") (pinfunction "DQ2_P23") (pintype "bidirectional"))
      (node (ref "U1") (pin "P8") (pinfunction "IO_L21N_7_P8") (pintype "bidirectional"))
    )
    (net (code "88") (name "Net-(U$1-DQ3)") (class "Default")
      (node (ref "U$1") (pin "P25") (pinfunction "DQ3_P25") (pintype "bidirectional"))
      (node (ref "U1") (pin "P10") (pinfunction "IO_L22P_7_P10") (pintype "bidirectional"))
    )
    (net (code "89") (name "Net-(U$1-DQ4)") (class "Default")
      (node (ref "U$1") (pin "P26") (pinfunction "DQ4_P26") (pintype "bidirectional"))
      (node (ref "U1") (pin "P11") (pinfunction "IO_L22N_7_P11") (pintype "bidirectional"))
    )
    (net (code "90") (name "Net-(U$1-DQ5)") (class "Default")
      (node (ref "U$1") (pin "P27") (pinfunction "DQ5_P27") (pintype "bidirectional"))
      (node (ref "U1") (pin "P12") (pinfunction "IO_L23P_7_P12") (pintype "bidirectional"))
    )
    (net (code "91") (name "Net-(U$1-DQ6)") (class "Default")
      (node (ref "U$1") (pin "P28") (pinfunction "DQ6_P28") (pintype "bidirectional"))
      (node (ref "U1") (pin "P13") (pinfunction "IO_L23N_7_P13") (pintype "bidirectional"))
    )
    (net (code "92") (name "Net-(U$1-DQ7)") (class "Default")
      (node (ref "U$1") (pin "P29") (pinfunction "DQ7_P29") (pintype "bidirectional"))
      (node (ref "U1") (pin "P14") (pinfunction "IO_L24P_7_P14") (pintype "bidirectional"))
    )
    (net (code "93") (name "Net-(U$1-OE)") (class "Default")
      (node (ref "U$1") (pin "P32") (pinfunction "OE_P32") (pintype "bidirectional"))
      (node (ref "U1") (pin "P17") (pinfunction "IO_L40P_7_P17") (pintype "bidirectional"))
    )
    (net (code "94") (name "Net-(U$1-WE)") (class "Default")
      (node (ref "U$1") (pin "P5") (pinfunction "WE_P5") (pintype "bidirectional"))
      (node (ref "U1") (pin "P24") (pinfunction "IO_L24N_6VREF_6_P24") (pintype "bidirectional"))
    )
    (net (code "95") (name "Net-(U1D-IO_L01N_2VRP_2)") (class "Default")
      (node (ref "JP1") (pin "1") (pinfunction "1_1") (pintype "passive"))
      (node (ref "U1") (pin "P108") (pinfunction "IO_L01N_2VRP_2_P108") (pintype "bidirectional"))
    )
    (net (code "96") (name "Net-(U1F-IO)") (class "Default")
      (node (ref "JP1") (pin "37") (pinfunction "37_37") (pintype "passive"))
      (node (ref "U1") (pin "P76") (pinfunction "IO_P76") (pintype "bidirectional"))
    )
    (net (code "97") (name "Net-(U1F-IO_L01N_3VRP_3)") (class "Default")
      (node (ref "JP1") (pin "40") (pinfunction "40_40") (pintype "passive"))
      (node (ref "U1") (pin "P74") (pinfunction "IO_L01N_3VRP_3_P74") (pintype "bidirectional"))
    )
    (net (code "98") (name "Net-(U1F-IO_L01P_3VRN_3)") (class "Default")
      (node (ref "JP1") (pin "39") (pinfunction "39_39") (pintype "passive"))
      (node (ref "U1") (pin "P73") (pinfunction "IO_L01P_3VRN_3_P73") (pintype "bidirectional"))
    )
    (net (code "99") (name "Net-(U1F-IO_L20N_3)") (class "Default")
      (node (ref "JP1") (pin "35") (pinfunction "35_35") (pintype "passive"))
      (node (ref "U1") (pin "P78") (pinfunction "IO_L20N_3_P78") (pintype "bidirectional"))
    )
    (net (code "100") (name "Net-(U1F-IO_L20P_3)") (class "Default")
      (node (ref "JP1") (pin "38") (pinfunction "38_38") (pintype "passive"))
      (node (ref "U1") (pin "P77") (pinfunction "IO_L20P_3_P77") (pintype "bidirectional"))
    )
    (net (code "101") (name "Net-(U1F-IO_L21N_3)") (class "Default")
      (node (ref "JP1") (pin "33") (pinfunction "33_33") (pintype "passive"))
      (node (ref "U1") (pin "P80") (pinfunction "IO_L21N_3_P80") (pintype "bidirectional"))
    )
    (net (code "102") (name "Net-(U1F-IO_L21P_3)") (class "Default")
      (node (ref "JP1") (pin "36") (pinfunction "36_36") (pintype "passive"))
      (node (ref "U1") (pin "P79") (pinfunction "IO_L21P_3_P79") (pintype "bidirectional"))
    )
    (net (code "103") (name "Net-(U1F-IO_L22N_3)") (class "Default")
      (node (ref "JP1") (pin "31") (pinfunction "31_31") (pintype "passive"))
      (node (ref "U1") (pin "P83") (pinfunction "IO_L22N_3_P83") (pintype "bidirectional"))
    )
    (net (code "104") (name "Net-(U1F-IO_L22P_3)") (class "Default")
      (node (ref "JP1") (pin "34") (pinfunction "34_34") (pintype "passive"))
      (node (ref "U1") (pin "P82") (pinfunction "IO_L22P_3_P82") (pintype "bidirectional"))
    )
    (net (code "105") (name "Net-(U1F-IO_L23N_3)") (class "Default")
      (node (ref "JP1") (pin "29") (pinfunction "29_29") (pintype "passive"))
      (node (ref "U1") (pin "P85") (pinfunction "IO_L23N_3_P85") (pintype "bidirectional"))
    )
    (net (code "106") (name "Net-(U1F-IO_L23P_3VREF_3)") (class "Default")
      (node (ref "JP1") (pin "32") (pinfunction "32_32") (pintype "passive"))
      (node (ref "U1") (pin "P84") (pinfunction "IO_L23P_3VREF_3_P84") (pintype "bidirectional"))
    )
    (net (code "107") (name "Net-(U1F-IO_L24N_3)") (class "Default")
      (node (ref "JP1") (pin "27") (pinfunction "27_27") (pintype "passive"))
      (node (ref "U1") (pin "P87") (pinfunction "IO_L24N_3_P87") (pintype "bidirectional"))
    )
    (net (code "108") (name "Net-(U1F-IO_L24P_3)") (class "Default")
      (node (ref "JP1") (pin "30") (pinfunction "30_30") (pintype "passive"))
      (node (ref "U1") (pin "P86") (pinfunction "IO_L24P_3_P86") (pintype "bidirectional"))
    )
    (net (code "109") (name "Net-(U1F-IO_L40N_3VREF_3)") (class "Default")
      (node (ref "JP1") (pin "25") (pinfunction "25_25") (pintype "passive"))
      (node (ref "U1") (pin "P90") (pinfunction "IO_L40N_3VREF_3_P90") (pintype "bidirectional"))
    )
    (net (code "110") (name "Net-(U1F-IO_L40P_3)") (class "Default")
      (node (ref "JP1") (pin "28") (pinfunction "28_28") (pintype "passive"))
      (node (ref "U1") (pin "P89") (pinfunction "IO_L40P_3_P89") (pintype "bidirectional"))
    )
    (net (code "111") (name "Net-(U1G-IO_L32P_4GCLK0)") (class "Default")
      (node (ref "U$2") (pin "OUT") (pinfunction "OUT_OUT") (pintype "output"))
      (node (ref "U1") (pin "P55") (pinfunction "IO_L32P_4GCLK0_P55") (pintype "bidirectional"))
    )
    (net (code "112") (name "Net-(U1N-TCK)") (class "Default")
      (node (ref "R2") (pin "1") (pinfunction "1_1") (pintype "passive"))
      (node (ref "U1") (pin "P110") (pinfunction "TCK_P110") (pintype "bidirectional"))
    )
    (net (code "113") (name "Net-(U1N-TDI)") (class "Default")
      (node (ref "R1") (pin "1") (pinfunction "1_1") (pintype "passive"))
      (node (ref "U1") (pin "P144") (pinfunction "TDI_P144") (pintype "bidirectional"))
    )
    (net (code "114") (name "Net-(U1N-TMS)") (class "Default")
      (node (ref "R3") (pin "1") (pinfunction "1_1") (pintype "passive"))
      (node (ref "U1") (pin "P111") (pinfunction "TMS_P111") (pintype "bidirectional"))
    )
    (net (code "115") (name "unconnected-(IC1-NC.1-Pad2)") (class "Default")
      (node (ref "IC1") (pin "2") (pinfunction "NC.1_2") (pintype "bidirectional"))
    )
    (net (code "116") (name "unconnected-(IC1-NC.2-Pad9)") (class "Default")
      (node (ref "IC1") (pin "9") (pinfunction "NC.2_9") (pintype "bidirectional"))
    )
    (net (code "117") (name "unconnected-(IC1-NC.3-Pad12)") (class "Default")
      (node (ref "IC1") (pin "12") (pinfunction "NC.3_12") (pintype "bidirectional"))
    )
    (net (code "118") (name "unconnected-(IC1-NC.4-Pad14)") (class "Default")
      (node (ref "IC1") (pin "14") (pinfunction "NC.4_14") (pintype "bidirectional"))
    )
    (net (code "119") (name "unconnected-(IC1-NC.5-Pad15)") (class "Default")
      (node (ref "IC1") (pin "15") (pinfunction "NC.5_15") (pintype "bidirectional"))
    )
    (net (code "120") (name "unconnected-(IC1-NC.6-Pad16)") (class "Default")
      (node (ref "IC1") (pin "16") (pinfunction "NC.6_16") (pintype "bidirectional"))
    )
    (net (code "121") (name "unconnected-(IC1-{slash}CEO-Pad13)") (class "Default")
      (node (ref "IC1") (pin "13") (pinfunction "/CEO_13") (pintype "bidirectional"))
    )
    (net (code "122") (name "unconnected-(JP1-Pad2)") (class "Default")
      (node (ref "JP1") (pin "2") (pinfunction "2_2") (pintype "passive"))
    )
    (net (code "123") (name "unconnected-(JP1-Pad3)") (class "Default")
      (node (ref "JP1") (pin "3") (pinfunction "3_3") (pintype "passive"))
    )
    (net (code "124") (name "unconnected-(JP1-Pad4)") (class "Default")
      (node (ref "JP1") (pin "4") (pinfunction "4_4") (pintype "passive"))
    )
    (net (code "125") (name "unconnected-(JP1-Pad5)") (class "Default")
      (node (ref "JP1") (pin "5") (pinfunction "5_5") (pintype "passive"))
    )
    (net (code "126") (name "unconnected-(JP1-Pad6)") (class "Default")
      (node (ref "JP1") (pin "6") (pinfunction "6_6") (pintype "passive"))
    )
    (net (code "127") (name "unconnected-(JP1-Pad7)") (class "Default")
      (node (ref "JP1") (pin "7") (pinfunction "7_7") (pintype "passive"))
    )
    (net (code "128") (name "unconnected-(JP1-Pad8)") (class "Default")
      (node (ref "JP1") (pin "8") (pinfunction "8_8") (pintype "passive"))
    )
    (net (code "129") (name "unconnected-(JP1-Pad9)") (class "Default")
      (node (ref "JP1") (pin "9") (pinfunction "9_9") (pintype "passive"))
    )
    (net (code "130") (name "unconnected-(JP1-Pad10)") (class "Default")
      (node (ref "JP1") (pin "10") (pinfunction "10_10") (pintype "passive"))
    )
    (net (code "131") (name "unconnected-(JP1-Pad11)") (class "Default")
      (node (ref "JP1") (pin "11") (pinfunction "11_11") (pintype "passive"))
    )
    (net (code "132") (name "unconnected-(JP1-Pad12)") (class "Default")
      (node (ref "JP1") (pin "12") (pinfunction "12_12") (pintype "passive"))
    )
    (net (code "133") (name "unconnected-(JP1-Pad13)") (class "Default")
      (node (ref "JP1") (pin "13") (pinfunction "13_13") (pintype "passive"))
    )
    (net (code "134") (name "unconnected-(JP1-Pad14)") (class "Default")
      (node (ref "JP1") (pin "14") (pinfunction "14_14") (pintype "passive"))
    )
    (net (code "135") (name "unconnected-(JP1-Pad15)") (class "Default")
      (node (ref "JP1") (pin "15") (pinfunction "15_15") (pintype "passive"))
    )
    (net (code "136") (name "unconnected-(JP1-Pad16)") (class "Default")
      (node (ref "JP1") (pin "16") (pinfunction "16_16") (pintype "passive"))
    )
    (net (code "137") (name "unconnected-(JP1-Pad17)") (class "Default")
      (node (ref "JP1") (pin "17") (pinfunction "17_17") (pintype "passive"))
    )
    (net (code "138") (name "unconnected-(JP1-Pad18)") (class "Default")
      (node (ref "JP1") (pin "18") (pinfunction "18_18") (pintype "passive"))
    )
    (net (code "139") (name "unconnected-(JP1-Pad19)") (class "Default")
      (node (ref "JP1") (pin "19") (pinfunction "19_19") (pintype "passive"))
    )
    (net (code "140") (name "unconnected-(JP1-Pad20)") (class "Default")
      (node (ref "JP1") (pin "20") (pinfunction "20_20") (pintype "passive"))
    )
    (net (code "141") (name "unconnected-(JP1-Pad21)") (class "Default")
      (node (ref "JP1") (pin "21") (pinfunction "21_21") (pintype "passive"))
    )
    (net (code "142") (name "unconnected-(JP1-Pad22)") (class "Default")
      (node (ref "JP1") (pin "22") (pinfunction "22_22") (pintype "passive"))
    )
    (net (code "143") (name "unconnected-(JP1-Pad23)") (class "Default")
      (node (ref "JP1") (pin "23") (pinfunction "23_23") (pintype "passive"))
    )
    (net (code "144") (name "unconnected-(JP1-Pad24)") (class "Default")
      (node (ref "JP1") (pin "24") (pinfunction "24_24") (pintype "passive"))
    )
    (net (code "145") (name "unconnected-(JP1-Pad26)") (class "Default")
      (node (ref "JP1") (pin "26") (pinfunction "26_26") (pintype "passive"))
    )
    (net (code "146") (name "unconnected-(U$2-TRI-PadENA)") (class "Default")
      (node (ref "U$2") (pin "ENA") (pinfunction "TRI_ENA") (pintype "input"))
    )
    (net (code "147") (name "unconnected-(U$3-VOUT2-Pad2)") (class "Default")
      (node (ref "U$3") (pin "2") (pinfunction "VOUT2_2") (pintype "bidirectional"))
    )
    (net (code "148") (name "unconnected-(U$4-VOUT2-Pad2)") (class "Default")
      (node (ref "U$4") (pin "2") (pinfunction "VOUT2_2") (pintype "bidirectional"))
    )
    (net (code "149") (name "unconnected-(U$5-PadP$1)") (class "Default")
      (node (ref "U$5") (pin "P$1") (pinfunction "P$1_P$1") (pintype "bidirectional"))
    )
    (net (code "150") (name "unconnected-(U$5-PadP$2)") (class "Default")
      (node (ref "U$5") (pin "P$2") (pinfunction "P$2_P$2") (pintype "bidirectional"))
    )
    (net (code "151") (name "unconnected-(U$5-PadP$3)") (class "Default")
      (node (ref "U$5") (pin "P$3") (pinfunction "P$3_P$3") (pintype "bidirectional"))
    )
    (net (code "152") (name "unconnected-(U$5-PadP$4)") (class "Default")
      (node (ref "U$5") (pin "P$4") (pinfunction "P$4_P$4") (pintype "bidirectional"))
    )
    (net (code "153") (name "unconnected-(U$5-PadP$5)") (class "Default")
      (node (ref "U$5") (pin "P$5") (pinfunction "P$5_P$5") (pintype "bidirectional"))
    )
    (net (code "154") (name "unconnected-(U$5-PadP$6)") (class "Default")
      (node (ref "U$5") (pin "P$6") (pinfunction "P$6_P$6") (pintype "bidirectional"))
    )
    (net (code "155") (name "unconnected-(U$5-PadP$7)") (class "Default")
      (node (ref "U$5") (pin "P$7") (pinfunction "P$7_P$7") (pintype "bidirectional"))
    )
    (net (code "156") (name "unconnected-(U$5-PadP$8)") (class "Default")
      (node (ref "U$5") (pin "P$8") (pinfunction "P$8_P$8") (pintype "bidirectional"))
    )
    (net (code "157") (name "unconnected-(U$5-PadP$9)") (class "Default")
      (node (ref "U$5") (pin "P$9") (pinfunction "P$9_P$9") (pintype "bidirectional"))
    )
    (net (code "158") (name "unconnected-(U$5-PadP$10)") (class "Default")
      (node (ref "U$5") (pin "P$10") (pinfunction "P$10_P$10") (pintype "bidirectional"))
    )
    (net (code "159") (name "unconnected-(U$5-PadP$11)") (class "Default")
      (node (ref "U$5") (pin "P$11") (pinfunction "P$11_P$11") (pintype "bidirectional"))
    )
    (net (code "160") (name "unconnected-(U$5-PadP$12)") (class "Default")
      (node (ref "U$5") (pin "P$12") (pinfunction "P$12_P$12") (pintype "bidirectional"))
    )
    (net (code "161") (name "unconnected-(U$5-PadP$13)") (class "Default")
      (node (ref "U$5") (pin "P$13") (pinfunction "P$13_P$13") (pintype "bidirectional"))
    )
    (net (code "162") (name "unconnected-(U$5-PadP$14)") (class "Default")
      (node (ref "U$5") (pin "P$14") (pinfunction "P$14_P$14") (pintype "bidirectional"))
    )
    (net (code "163") (name "unconnected-(U$5-PadP$15)") (class "Default")
      (node (ref "U$5") (pin "P$15") (pinfunction "P$15_P$15") (pintype "bidirectional"))
    )
    (net (code "164") (name "unconnected-(U$5-PadP$16)") (class "Default")
      (node (ref "U$5") (pin "P$16") (pinfunction "P$16_P$16") (pintype "bidirectional"))
    )
    (net (code "165") (name "unconnected-(U$5-PadP$17)") (class "Default")
      (node (ref "U$5") (pin "P$17") (pinfunction "P$17_P$17") (pintype "bidirectional"))
    )
    (net (code "166") (name "unconnected-(U$5-PadP$18)") (class "Default")
      (node (ref "U$5") (pin "P$18") (pinfunction "P$18_P$18") (pintype "bidirectional"))
    )
    (net (code "167") (name "unconnected-(U$5-PadP$19)") (class "Default")
      (node (ref "U$5") (pin "P$19") (pinfunction "P$19_P$19") (pintype "bidirectional"))
    )
    (net (code "168") (name "unconnected-(U$5-PadP$20)") (class "Default")
      (node (ref "U$5") (pin "P$20") (pinfunction "P$20_P$20") (pintype "bidirectional"))
    )
    (net (code "169") (name "unconnected-(U$5B-P$1-PadP$21)") (class "Default")
      (node (ref "U$5") (pin "P$21") (pinfunction "P$1_P$21") (pintype "bidirectional"))
    )
    (net (code "170") (name "unconnected-(U$5B-P$2-PadP$22)") (class "Default")
      (node (ref "U$5") (pin "P$22") (pinfunction "P$2_P$22") (pintype "bidirectional"))
    )
    (net (code "171") (name "unconnected-(U$5B-P$3-PadP$23)") (class "Default")
      (node (ref "U$5") (pin "P$23") (pinfunction "P$3_P$23") (pintype "bidirectional"))
    )
    (net (code "172") (name "unconnected-(U$5B-P$4-PadP$24)") (class "Default")
      (node (ref "U$5") (pin "P$24") (pinfunction "P$4_P$24") (pintype "bidirectional"))
    )
    (net (code "173") (name "unconnected-(U$5B-P$5-PadP$25)") (class "Default")
      (node (ref "U$5") (pin "P$25") (pinfunction "P$5_P$25") (pintype "bidirectional"))
    )
    (net (code "174") (name "unconnected-(U$5B-P$6-PadP$26)") (class "Default")
      (node (ref "U$5") (pin "P$26") (pinfunction "P$6_P$26") (pintype "bidirectional"))
    )
    (net (code "175") (name "unconnected-(U$5B-P$7-PadP$27)") (class "Default")
      (node (ref "U$5") (pin "P$27") (pinfunction "P$7_P$27") (pintype "bidirectional"))
    )
    (net (code "176") (name "unconnected-(U$5B-P$8-PadP$28)") (class "Default")
      (node (ref "U$5") (pin "P$28") (pinfunction "P$8_P$28") (pintype "bidirectional"))
    )
    (net (code "177") (name "unconnected-(U$5B-P$9-PadP$29)") (class "Default")
      (node (ref "U$5") (pin "P$29") (pinfunction "P$9_P$29") (pintype "bidirectional"))
    )
    (net (code "178") (name "unconnected-(U$5B-P$10-PadP$30)") (class "Default")
      (node (ref "U$5") (pin "P$30") (pinfunction "P$10_P$30") (pintype "bidirectional"))
    )
    (net (code "179") (name "unconnected-(U$5B-P$11-PadP$31)") (class "Default")
      (node (ref "U$5") (pin "P$31") (pinfunction "P$11_P$31") (pintype "bidirectional"))
    )
    (net (code "180") (name "unconnected-(U$5B-P$12-PadP$32)") (class "Default")
      (node (ref "U$5") (pin "P$32") (pinfunction "P$12_P$32") (pintype "bidirectional"))
    )
    (net (code "181") (name "unconnected-(U$5B-P$13-PadP$33)") (class "Default")
      (node (ref "U$5") (pin "P$33") (pinfunction "P$13_P$33") (pintype "bidirectional"))
    )
    (net (code "182") (name "unconnected-(U$5B-P$14-PadP$34)") (class "Default")
      (node (ref "U$5") (pin "P$34") (pinfunction "P$14_P$34") (pintype "bidirectional"))
    )
    (net (code "183") (name "unconnected-(U$5B-P$15-PadP$35)") (class "Default")
      (node (ref "U$5") (pin "P$35") (pinfunction "P$15_P$35") (pintype "bidirectional"))
    )
    (net (code "184") (name "unconnected-(U$5B-P$16-PadP$36)") (class "Default")
      (node (ref "U$5") (pin "P$36") (pinfunction "P$16_P$36") (pintype "bidirectional"))
    )
    (net (code "185") (name "unconnected-(U$5B-P$17-PadP$37)") (class "Default")
      (node (ref "U$5") (pin "P$37") (pinfunction "P$17_P$37") (pintype "bidirectional"))
    )
    (net (code "186") (name "unconnected-(U$5B-P$18-PadP$38)") (class "Default")
      (node (ref "U$5") (pin "P$38") (pinfunction "P$18_P$38") (pintype "bidirectional"))
    )
    (net (code "187") (name "unconnected-(U$5B-P$19-PadP$39)") (class "Default")
      (node (ref "U$5") (pin "P$39") (pinfunction "P$19_P$39") (pintype "bidirectional"))
    )
    (net (code "188") (name "unconnected-(U$5B-P$20-PadP$40)") (class "Default")
      (node (ref "U$5") (pin "P$40") (pinfunction "P$20_P$40") (pintype "bidirectional"))
    )
    (net (code "189") (name "unconnected-(U1A-IO_L01N_0VRP_0-PadP141)") (class "Default")
      (node (ref "U1") (pin "P141") (pinfunction "IO_L01N_0VRP_0_P141") (pintype "bidirectional"))
    )
    (net (code "190") (name "unconnected-(U1A-IO_L01P_0VRN_0-PadP140)") (class "Default")
      (node (ref "U1") (pin "P140") (pinfunction "IO_L01P_0VRN_0_P140") (pintype "bidirectional"))
    )
    (net (code "191") (name "unconnected-(U1A-IO_L27N_0-PadP137)") (class "Default")
      (node (ref "U1") (pin "P137") (pinfunction "IO_L27N_0_P137") (pintype "bidirectional"))
    )
    (net (code "192") (name "unconnected-(U1A-IO_L27P_0-PadP135)") (class "Default")
      (node (ref "U1") (pin "P135") (pinfunction "IO_L27P_0_P135") (pintype "bidirectional"))
    )
    (net (code "193") (name "unconnected-(U1A-IO_L30N_0-PadP132)") (class "Default")
      (node (ref "U1") (pin "P132") (pinfunction "IO_L30N_0_P132") (pintype "bidirectional"))
    )
    (net (code "194") (name "unconnected-(U1A-IO_L30P_0-PadP131)") (class "Default")
      (node (ref "U1") (pin "P131") (pinfunction "IO_L30P_0_P131") (pintype "bidirectional"))
    )
    (net (code "195") (name "unconnected-(U1A-IO_L31N_0-PadP130)") (class "Default")
      (node (ref "U1") (pin "P130") (pinfunction "IO_L31N_0_P130") (pintype "bidirectional"))
    )
    (net (code "196") (name "unconnected-(U1A-IO_L31P_0VREF_0-PadP129)") (class "Default")
      (node (ref "U1") (pin "P129") (pinfunction "IO_L31P_0VREF_0_P129") (pintype "bidirectional"))
    )
    (net (code "197") (name "unconnected-(U1A-IO_L32N_0GCLK7-PadP128)") (class "Default")
      (node (ref "U1") (pin "P128") (pinfunction "IO_L32N_0GCLK7_P128") (pintype "bidirectional"))
    )
    (net (code "198") (name "unconnected-(U1A-IO_L32P_0GCLK6-PadP127)") (class "Default")
      (node (ref "U1") (pin "P127") (pinfunction "IO_L32P_0GCLK6_P127") (pintype "bidirectional"))
    )
    (net (code "199") (name "unconnected-(U1C-IO-PadP116)") (class "Default")
      (node (ref "U1") (pin "P116") (pinfunction "IO_P116") (pintype "bidirectional"))
    )
    (net (code "200") (name "unconnected-(U1C-IO_L01N_1VRP_1-PadP113)") (class "Default")
      (node (ref "U1") (pin "P113") (pinfunction "IO_L01N_1VRP_1_P113") (pintype "bidirectional"))
    )
    (net (code "201") (name "unconnected-(U1C-IO_L01P_1VRN_1-PadP112)") (class "Default")
      (node (ref "U1") (pin "P112") (pinfunction "IO_L01P_1VRN_1_P112") (pintype "bidirectional"))
    )
    (net (code "202") (name "unconnected-(U1C-IO_L28N_1-PadP119)") (class "Default")
      (node (ref "U1") (pin "P119") (pinfunction "IO_L28N_1_P119") (pintype "bidirectional"))
    )
    (net (code "203") (name "unconnected-(U1C-IO_L28P_1-PadP118)") (class "Default")
      (node (ref "U1") (pin "P118") (pinfunction "IO_L28P_1_P118") (pintype "bidirectional"))
    )
    (net (code "204") (name "unconnected-(U1C-IO_L31N_1VREF_1-PadP123)") (class "Default")
      (node (ref "U1") (pin "P123") (pinfunction "IO_L31N_1VREF_1_P123") (pintype "bidirectional"))
    )
    (net (code "205") (name "unconnected-(U1C-IO_L31P_1-PadP122)") (class "Default")
      (node (ref "U1") (pin "P122") (pinfunction "IO_L31P_1_P122") (pintype "bidirectional"))
    )
    (net (code "206") (name "unconnected-(U1C-IO_L32N_1GCLK5-PadP125)") (class "Default")
      (node (ref "U1") (pin "P125") (pinfunction "IO_L32N_1GCLK5_P125") (pintype "bidirectional"))
    )
    (net (code "207") (name "unconnected-(U1C-IO_L32P_1GCLK4-PadP124)") (class "Default")
      (node (ref "U1") (pin "P124") (pinfunction "IO_L32P_1GCLK4_P124") (pintype "bidirectional"))
    )
    (net (code "208") (name "unconnected-(U1D-IO_L01P_2VRN_2-PadP107)") (class "Default")
      (node (ref "U1") (pin "P107") (pinfunction "IO_L01P_2VRN_2_P107") (pintype "bidirectional"))
    )
    (net (code "209") (name "unconnected-(U1D-IO_L20N_2-PadP105)") (class "Default")
      (node (ref "U1") (pin "P105") (pinfunction "IO_L20N_2_P105") (pintype "bidirectional"))
    )
    (net (code "210") (name "unconnected-(U1D-IO_L20P_2-PadP104)") (class "Default")
      (node (ref "U1") (pin "P104") (pinfunction "IO_L20P_2_P104") (pintype "bidirectional"))
    )
    (net (code "211") (name "unconnected-(U1D-IO_L21N_2-PadP103)") (class "Default")
      (node (ref "U1") (pin "P103") (pinfunction "IO_L21N_2_P103") (pintype "bidirectional"))
    )
    (net (code "212") (name "unconnected-(U1D-IO_L21P_2-PadP102)") (class "Default")
      (node (ref "U1") (pin "P102") (pinfunction "IO_L21P_2_P102") (pintype "bidirectional"))
    )
    (net (code "213") (name "unconnected-(U1D-IO_L22N_2-PadP100)") (class "Default")
      (node (ref "U1") (pin "P100") (pinfunction "IO_L22N_2_P100") (pintype "bidirectional"))
    )
    (net (code "214") (name "unconnected-(U1D-IO_L22P_2-PadP99)") (class "Default")
      (node (ref "U1") (pin "P99") (pinfunction "IO_L22P_2_P99") (pintype "bidirectional"))
    )
    (net (code "215") (name "unconnected-(U1D-IO_L23N_2VREF_2-PadP98)") (class "Default")
      (node (ref "U1") (pin "P98") (pinfunction "IO_L23N_2VREF_2_P98") (pintype "bidirectional"))
    )
    (net (code "216") (name "unconnected-(U1D-IO_L23P_2-PadP97)") (class "Default")
      (node (ref "U1") (pin "P97") (pinfunction "IO_L23P_2_P97") (pintype "bidirectional"))
    )
    (net (code "217") (name "unconnected-(U1D-IO_L24N_2-PadP96)") (class "Default")
      (node (ref "U1") (pin "P96") (pinfunction "IO_L24N_2_P96") (pintype "bidirectional"))
    )
    (net (code "218") (name "unconnected-(U1D-IO_L24P_2-PadP95)") (class "Default")
      (node (ref "U1") (pin "P95") (pinfunction "IO_L24P_2_P95") (pintype "bidirectional"))
    )
    (net (code "219") (name "unconnected-(U1D-IO_L40N_2-PadP93)") (class "Default")
      (node (ref "U1") (pin "P93") (pinfunction "IO_L40N_2_P93") (pintype "bidirectional"))
    )
    (net (code "220") (name "unconnected-(U1D-IO_L40P_2VREF_2-PadP92)") (class "Default")
      (node (ref "U1") (pin "P92") (pinfunction "IO_L40P_2VREF_2_P92") (pintype "bidirectional"))
    )
    (net (code "221") (name "unconnected-(U1G-IOVREF_4-PadP70)") (class "Default")
      (node (ref "U1") (pin "P70") (pinfunction "IOVREF_4_P70") (pintype "bidirectional"))
    )
    (net (code "222") (name "unconnected-(U1G-IO_L01N_4VRP_4-PadP69)") (class "Default")
      (node (ref "U1") (pin "P69") (pinfunction "IO_L01N_4VRP_4_P69") (pintype "bidirectional"))
    )
    (net (code "223") (name "unconnected-(U1G-IO_L01P_4VRN_4-PadP68)") (class "Default")
      (node (ref "U1") (pin "P68") (pinfunction "IO_L01P_4VRN_4_P68") (pintype "bidirectional"))
    )
    (net (code "224") (name "unconnected-(U1G-IO_L27P_4D1-PadP63)") (class "Default")
      (node (ref "U1") (pin "P63") (pinfunction "IO_L27P_4D1_P63") (pintype "bidirectional"))
    )
    (net (code "225") (name "unconnected-(U1G-IO_L30N_4D2-PadP60)") (class "Default")
      (node (ref "U1") (pin "P60") (pinfunction "IO_L30N_4D2_P60") (pintype "bidirectional"))
    )
    (net (code "226") (name "unconnected-(U1G-IO_L30P_4D3-PadP59)") (class "Default")
      (node (ref "U1") (pin "P59") (pinfunction "IO_L30P_4D3_P59") (pintype "bidirectional"))
    )
    (net (code "227") (name "unconnected-(U1G-IO_L31P_4DOUTBUSY-PadP57)") (class "Default")
      (node (ref "U1") (pin "P57") (pinfunction "IO_L31P_4DOUTBUSY_P57") (pintype "bidirectional"))
    )
    (net (code "228") (name "unconnected-(U1G-IO_L32N_4GCLK1-PadP56)") (class "Default")
      (node (ref "U1") (pin "P56") (pinfunction "IO_L32N_4GCLK1_P56") (pintype "bidirectional"))
    )
    (net (code "229") (name "unconnected-(U1I-IOVREF_5-PadP44)") (class "Default")
      (node (ref "U1") (pin "P44") (pinfunction "IOVREF_5_P44") (pintype "bidirectional"))
    )
    (net (code "230") (name "unconnected-(U1I-IO_L01N_5RDWR_B-PadP41)") (class "Default")
      (node (ref "U1") (pin "P41") (pinfunction "IO_L01N_5RDWR_B_P41") (pintype "bidirectional"))
    )
    (net (code "231") (name "unconnected-(U1I-IO_L01P_5CS_B-PadP40)") (class "Default")
      (node (ref "U1") (pin "P40") (pinfunction "IO_L01P_5CS_B_P40") (pintype "bidirectional"))
    )
    (net (code "232") (name "unconnected-(U1I-IO_L28N_5D6-PadP47)") (class "Default")
      (node (ref "U1") (pin "P47") (pinfunction "IO_L28N_5D6_P47") (pintype "bidirectional"))
    )
    (net (code "233") (name "unconnected-(U1I-IO_L28P_5D7-PadP46)") (class "Default")
      (node (ref "U1") (pin "P46") (pinfunction "IO_L28P_5D7_P46") (pintype "bidirectional"))
    )
    (net (code "234") (name "unconnected-(U1I-IO_L31N_5D4-PadP51)") (class "Default")
      (node (ref "U1") (pin "P51") (pinfunction "IO_L31N_5D4_P51") (pintype "bidirectional"))
    )
    (net (code "235") (name "unconnected-(U1I-IO_L31P_5D5-PadP50)") (class "Default")
      (node (ref "U1") (pin "P50") (pinfunction "IO_L31P_5D5_P50") (pintype "bidirectional"))
    )
    (net (code "236") (name "unconnected-(U1I-IO_L32N_5GCLK3-PadP53)") (class "Default")
      (node (ref "U1") (pin "P53") (pinfunction "IO_L32N_5GCLK3_P53") (pintype "bidirectional"))
    )
    (net (code "237") (name "unconnected-(U1I-IO_L32P_5GCLK2-PadP52)") (class "Default")
      (node (ref "U1") (pin "P52") (pinfunction "IO_L32P_5GCLK2_P52") (pintype "bidirectional"))
    )
    (net (code "238") (name "unconnected-(U1N-HSWAP_EN-PadP142)") (class "Default")
      (node (ref "U1") (pin "P142") (pinfunction "HSWAP_EN_P142") (pintype "bidirectional"))
    )
    (net (code "239") (name "unconnected-(X1-3-Pad2)") (class "Default")
      (node (ref "X1") (pin "2") (pinfunction "3_2") (pintype "passive"))
    )
    (net (code "240") (name "unconnected-(X2-Pad10)") (class "Default")
      (node (ref "X2") (pin "10") (pinfunction "10_10") (pintype "passive"))
    )
    (net (code "241") (name "unconnected-(X2-Pad12)") (class "Default")
      (node (ref "X2") (pin "12") (pinfunction "12_12") (pintype "passive"))
    )
    (net (code "242") (name "unconnected-(X3-Pad2)") (class "Default")
      (node (ref "X3") (pin "2") (pinfunction "2_2") (pintype "passive"))
    )
    (net (code "243") (name "unconnected-(X3-Pad8)") (class "Default")
      (node (ref "X3") (pin "8") (pinfunction "8_8") (pintype "passive"))
    )
  )
)
